# 1.net
KiCad netlist of a schematic drawn in Altium Designer
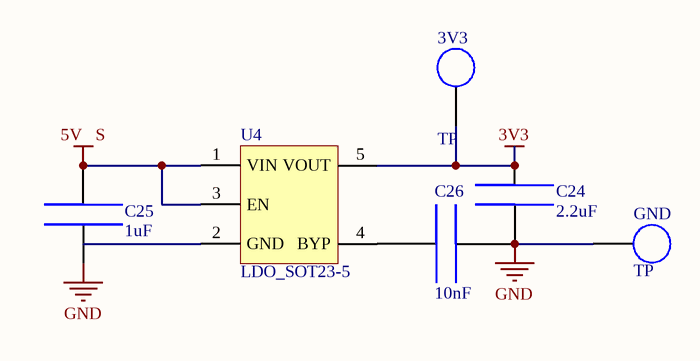
[diagram p0: （1）.SchDoc]

(export (version "E")
  (design (tool "Eeschema 10.0.6"))
  (components
    (comp (ref "3V3") (value "TP") (libsource (lib "袁琦越(1)Schlib1") (part "?")))
    (comp (ref "C24") (value "2.2uF") (description "电容2") (libsource (lib "袁琦越(1)Schlib1") (part "CAP2")))
    (comp (ref "C25") (value "1uF") (description "电容1") (libsource (lib "袁琦越(1)Schlib1") (part "CAP1")))
    (comp (ref "C26") (value "10nF") (description "电容3") (libsource (lib "袁琦越(1)Schlib1") (part "CAP3")))
    (comp (ref "GND") (value "TP") (libsource (lib "袁琦越(1)Schlib1") (part "!")))
    (comp (ref "U4")
      (value "LDO_SOT23-5")
      (footprint "SOT-23 L")
      (libsource (lib "mycomponents") (part "LDO_SOT23-5"))
    )
  )
  (nets
    (net (code "1") (name "3V3") (class "Default")
      (node (ref "3V3") (pin "1") (pinfunction "1_1") (pintype "passive"))
      (node (ref "C24") (pin "2") (pinfunction "2_2") (pintype "passive"))
      (node (ref "U4") (pin "5") (pinfunction "VOUT_5") (pintype "passive"))
    )
    (net (code "2") (name "5V   S") (class "Default")
      (node (ref "C25") (pin "2") (pinfunction "2_2") (pintype "passive"))
      (node (ref "U4") (pin "1") (pinfunction "VIN_1") (pintype "passive"))
      (node (ref "U4") (pin "3") (pinfunction "EN_3") (pintype "passive"))
    )
    (net (code "3") (name "GND") (class "Default")
      (node (ref "C24") (pin "1") (pinfunction "1_1") (pintype "passive"))
      (node (ref "C25") (pin "1") (pinfunction "1_1") (pintype "passive"))
      (node (ref "C26") (pin "2") (pinfunction "2_2") (pintype "passive"))
      (node (ref "GND") (pin "1") (pinfunction "1_1") (pintype "passive"))
    )
    (net (code "4") (name "Net-(U4-BYP)") (class "Default")
      (node (ref "C26") (pin "1") (pinfunction "1_1") (pintype "passive"))
      (node (ref "U4") (pin "4") (pinfunction "BYP_4") (pintype "passive"))
    )
    (net (code "5") (name "unconnected-(U4-GND-Pad2)") (class "Default")
      (node (ref "U4") (pin "2") (pinfunction "GND_2") (pintype "passive"))
    )
  )
)
